# PR9027.net
KiCad netlist of a schematic drawn in EAGLE
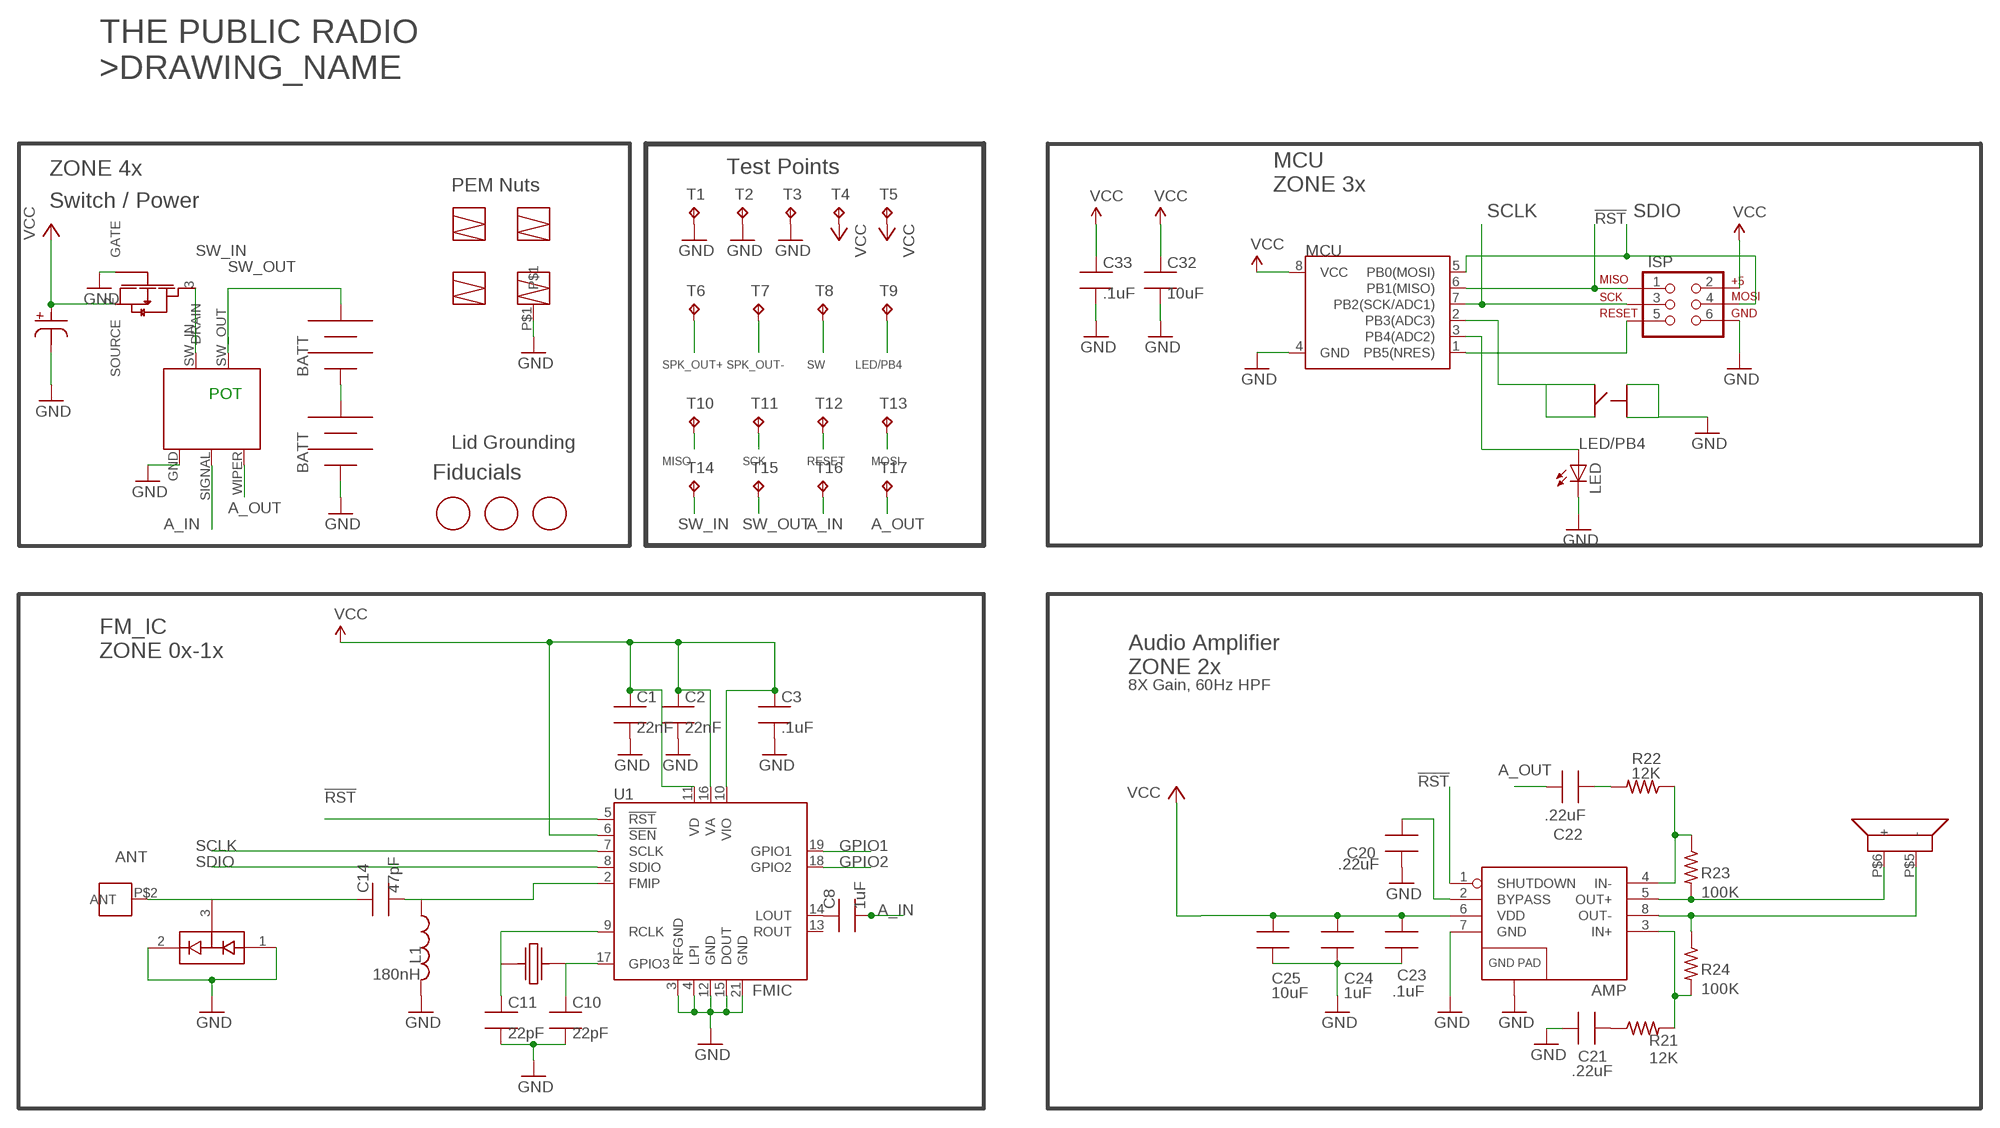
[diagram p0: schematic, sheet 1]

(export (version "E")
  (design (tool "Eeschema 10.0.6"))
  (components
    (comp (ref "AMP")
      (value "TPA6203A1")
      (footprint "eagle-import:8-MSOP")
      (libsource (lib "eagle-import") (part "TPA6203A1"))
    )
    (comp (ref "ANT_MOUNT")
      (value "PEM_M3")
      (footprint "eagle-import:PEM_M3")
      (libsource (lib "eagle-import") (part "PEM_M3"))
    )
    (comp (ref "C1")
      (value "22nF")
      (footprint "eagle-import:0603_CPL")
      (fields
        (field (name "MFG_PN") "CL10B223KB8NNNC")
        (field (name "TOL") "10%")
        (field (name "VOLTAGE") "16V")
      )
      (libsource (lib "eagle-import") (part "C_SMT_0603_CPL"))
    )
    (comp (ref "C2")
      (value "22nF")
      (footprint "eagle-import:0603_CPL")
      (fields
        (field (name "MFG_PN") "CL10B223KB8NNNC")
        (field (name "TOL") "10%")
        (field (name "VOLTAGE") "16V")
      )
      (libsource (lib "eagle-import") (part "C_SMT_0603_CPL"))
    )
    (comp (ref "C3")
      (value ".1uF")
      (footprint "eagle-import:0603_CPL")
      (fields
        (field (name "MFG_PN") "CL10B104KB8SFNC")
        (field (name "TOL") "10%")
        (field (name "VOLTAGE") "16V")
      )
      (libsource (lib "eagle-import") (part "C_SMT_0603_CPL"))
    )
    (comp (ref "C8")
      (value "1uF")
      (footprint "eagle-import:0603_CPL")
      (fields
        (field (name "MFG_PN") "CL10B105KP8NNNC")
        (field (name "TOL") "10%")
        (field (name "VOLTAGE") "10V")
      )
      (libsource (lib "eagle-import") (part "C_SMT_0603_CPL"))
    )
    (comp (ref "C10")
      (value "22pF")
      (footprint "eagle-import:0603_CPL")
      (fields
        (field (name "MFG_PN") "C1608C0G1H220J080AA")
        (field (name "TOL") "5%")
        (field (name "VOLTAGE") "50V")
      )
      (libsource (lib "eagle-import") (part "C_SMT_0603_CPL"))
    )
    (comp (ref "C11")
      (value "22pF")
      (footprint "eagle-import:0603_CPL")
      (fields
        (field (name "MFG_PN") "C1608C0G1H220J080AA")
        (field (name "TOL") "5%")
        (field (name "VOLTAGE") "50V")
      )
      (libsource (lib "eagle-import") (part "C_SMT_0603_CPL"))
    )
    (comp (ref "C14")
      (value "47pF")
      (footprint "eagle-import:0603_CPL")
      (fields
        (field (name "MFG_PN") "CL10C470JB8NCNC")
        (field (name "TOL") "5%")
        (field (name "VOLTAGE") "50V")
      )
      (libsource (lib "eagle-import") (part "C_SMT_0603_CPL"))
    )
    (comp (ref "C20")
      (value ".22uF")
      (footprint "eagle-import:0603_CPL")
      (fields
        (field (name "MFG_PN") "C1608X7R1C224K080AC")
        (field (name "TOL") "10%")
        (field (name "VOLTAGE") "16V")
      )
      (libsource (lib "eagle-import") (part "C_SMT_0603_CPL"))
    )
    (comp (ref "C21")
      (value ".22uF")
      (footprint "eagle-import:0603_CPL")
      (fields
        (field (name "MFG_PN") "C1608X7R1C224K080AC")
        (field (name "TOL") "10%")
        (field (name "VOLTAGE") "16V")
      )
      (libsource (lib "eagle-import") (part "C_SMT_0603_CPL"))
    )
    (comp (ref "C22")
      (value ".22uF")
      (footprint "eagle-import:0603_CPL")
      (fields
        (field (name "MFG_PN") "C1608X7R1C224K080AC")
        (field (name "TOL") "10%")
        (field (name "VOLTAGE") "16V")
      )
      (libsource (lib "eagle-import") (part "C_SMT_0603_CPL"))
    )
    (comp (ref "C23")
      (value ".1uF")
      (footprint "eagle-import:0603_CPL")
      (fields
        (field (name "MFG_PN") "CL10B104KB8SFNC")
        (field (name "TOL") "10%")
        (field (name "VOLTAGE") "16V")
      )
      (libsource (lib "eagle-import") (part "C_SMT_0603_CPL"))
    )
    (comp (ref "C24")
      (value "1uF")
      (footprint "eagle-import:0603_CPL")
      (fields
        (field (name "MFG_PN") "CL10B105KP8NNNC")
        (field (name "TOL") "10%")
        (field (name "VOLTAGE") "10V")
      )
      (libsource (lib "eagle-import") (part "C_SMT_0603_CPL"))
    )
    (comp (ref "C25")
      (value "10uF")
      (footprint "eagle-import:0603_CPL")
      (fields
        (field (name "MFG_PN") "CL10A106MQ8NNNC")
        (field (name "TOL") "20%")
        (field (name "VOLTAGE") "6.3V")
      )
      (libsource (lib "eagle-import") (part "C_SMT_0603_CPL"))
    )
    (comp (ref "C32")
      (value "10uF")
      (footprint "eagle-import:0603_CPL")
      (fields
        (field (name "MFG_PN") "CL10A106MQ8NNNC")
        (field (name "TOL") "20%")
        (field (name "VOLTAGE") "6.3V")
      )
      (libsource (lib "eagle-import") (part "C_SMT_0603_CPL"))
    )
    (comp (ref "C33")
      (value ".1uF")
      (footprint "eagle-import:0603_CPL")
      (fields
        (field (name "MFG_PN") "CL10B104KB8SFNC")
        (field (name "TOL") "10%")
        (field (name "VOLTAGE") "16V")
      )
      (libsource (lib "eagle-import") (part "C_SMT_0603_CPL"))
    )
    (comp (ref "C40")
      (value "220uF")
      (footprint "eagle-import:NICHICON_UD_63")
      (fields (field (name "TOL") "20%") (field (name "VOLTAGE") "16V"))
      (libsource (lib "eagle-import") (part "NICHICON_SERIESUD"))
    )
    (comp (ref "D1")
      (value "BAV99")
      (footprint "eagle-import:SOT23_CPL")
      (fields (field (name "MFG_PN") "BAV99,215"))
      (libsource (lib "eagle-import") (part "BAV99"))
    )
    (comp (ref "FET1")
      (value "AO3435")
      (footprint "eagle-import:SOT23_CPL")
      (fields (field (name "MFG_PN") "AO3435"))
      (libsource (lib "eagle-import") (part "AO3435"))
    )
    (comp (ref "ISP")
      (value "AVR_SPI_PRG_6NS")
      (footprint "eagle-import:2X3-NS")
      (fields (field (name "MFG_PN") "DNP"))
      (libsource (lib "eagle-import") (part "AVR_SPI_PRG_6NS"))
    )
    (comp (ref "JP5")
      (value "BK-92_MPD_AA_BATT_CLIP")
      (footprint "eagle-import:BK92_AA_BATT")
      (fields (field (name "MFG_PN") "Consigned"))
      (libsource (lib "eagle-import") (part "BK-92_MPD_AA_BATT_CLIP"))
    )
    (comp (ref "JP6")
      (value "BK-92_MPD_AA_BATT_CLIP")
      (footprint "eagle-import:BK92_AA_BATT")
      (fields (field (name "MFG_PN") "Consigned"))
      (libsource (lib "eagle-import") (part "BK-92_MPD_AA_BATT_CLIP"))
    )
    (comp (ref "L1")
      (value "180nH")
      (footprint "eagle-import:0805_ADAFRUIT")
      (fields
        (field (name "CURRENT") "400mA")
        (field (name "DCR") "640m")
        (field (name "MFG_PN") "AISC-0805-R18J-T ")
        (field (name "TOL") "5%")
      )
      (libsource (lib "eagle-import") (part "L_SMT_0805_ADAFRUIT"))
    )
    (comp (ref "LED")
      (value "HSMC-C265_REVERSE_MOUNT_LED")
      (footprint "eagle-import:HSMA-C265_REVERSE_MOUN_LED")
      (libsource (lib "eagle-import") (part "HSMC-C265_REVERSE_MOUNT_LED"))
    )
    (comp (ref "MARK1")
      (value "FIDUCIAL")
      (footprint "eagle-import:FIDUCIAL_1MM")
      (libsource (lib "eagle-import") (part "FIDUCIAL"))
    )
    (comp (ref "MARK2")
      (value "FIDUCIAL")
      (footprint "eagle-import:FIDUCIAL_1MM")
      (libsource (lib "eagle-import") (part "FIDUCIAL"))
    )
    (comp (ref "MARK3")
      (value "FIDUCIAL")
      (footprint "eagle-import:FIDUCIAL_1MM")
      (libsource (lib "eagle-import") (part "FIDUCIAL"))
    )
    (comp (ref "MCU")
      (value "ATTINY45TINY45-20-SMT")
      (footprint "eagle-import:8-SOIC")
      (fields (field (name "MFG_PN") "ATTINY25-20SUR "))
      (libsource (lib "eagle-import") (part "ATTINY45TINY45-20-SMT"))
    )
    (comp (ref "R1")
      (value "VOLUME_POT")
      (footprint "eagle-import:H17112NS_A10K_L20F-002")
      (libsource (lib "eagle-import") (part "VOLUME_POT"))
    )
    (comp (ref "R21")
      (value "12K")
      (footprint "eagle-import:0603_CPL")
      (fields
        (field (name "MFG_PN") "RC0603FR-0712KL")
        (field (name "POWER") "1/10W")
        (field (name "TOL") "1%")
      )
      (libsource (lib "eagle-import") (part "R_SMT_R0603_CPL"))
    )
    (comp (ref "R22")
      (value "12K")
      (footprint "eagle-import:0603_CPL")
      (fields
        (field (name "MFG_PN") "RC0603FR-0712KL")
        (field (name "POWER") "1/10W")
        (field (name "TOL") "1%")
      )
      (libsource (lib "eagle-import") (part "R_SMT_R0603_CPL"))
    )
    (comp (ref "R23")
      (value "100K")
      (footprint "eagle-import:0603_CPL")
      (fields
        (field (name "MFG_PN") "ERJ-3EKF1003V")
        (field (name "POWER") "1/10W")
        (field (name "TOL") "1%")
      )
      (libsource (lib "eagle-import") (part "R_SMT_R0603_CPL"))
    )
    (comp (ref "R24")
      (value "100K")
      (footprint "eagle-import:0603_CPL")
      (fields
        (field (name "MFG_PN") "ERJ-3EKF1003V")
        (field (name "POWER") "1/10W")
        (field (name "TOL") "1%")
      )
      (libsource (lib "eagle-import") (part "R_SMT_R0603_CPL"))
    )
    (comp (ref "SPEAKER")
      (value "PR2023_GROUND_UP_SPEAKER")
      (footprint "eagle-import:PR2023_GROUND_UP_SPEAKER")
      (libsource (lib "eagle-import") (part "PR2023_GROUND_UP_SPEAKER"))
    )
    (comp (ref "SPEAKER_PEM_1")
      (value "PEM_M3_ONE_SIDE")
      (footprint "eagle-import:PEM_M3_ONE_SIDE")
      (libsource (lib "eagle-import") (part "PEM_M3_ONE_SIDE"))
    )
    (comp (ref "SPEAKER_PEM_2")
      (value "PEM_M3_ONE_SIDE")
      (footprint "eagle-import:PEM_M3_ONE_SIDE")
      (libsource (lib "eagle-import") (part "PEM_M3_ONE_SIDE"))
    )
    (comp (ref "SPEAKER_PEM_3")
      (value "PEM_M3_ONE_SIDE_W/PIN")
      (footprint "eagle-import:PEM_M3_ONE_SIDE")
      (libsource (lib "eagle-import") (part "PEM_M3_ONE_SIDE_W/PIN"))
    )
    (comp (ref "SPEAKER_PEM_4")
      (value "PEM_M3_ONE_SIDE")
      (footprint "eagle-import:PEM_M3_ONE_SIDE")
      (libsource (lib "eagle-import") (part "PEM_M3_ONE_SIDE"))
    )
    (comp (ref "SW1")
      (value "C&K_PTS645")
      (footprint "eagle-import:C&K_PTS645_SMT")
      (libsource (lib "eagle-import") (part "C&K_PTS645"))
    )
    (comp (ref "T1")
      (value "TPTP20R")
      (footprint "eagle-import:TP20R")
      (libsource (lib "eagle-import") (part "TPTP20R"))
    )
    (comp (ref "T2")
      (value "TPTP20R")
      (footprint "eagle-import:TP20R")
      (libsource (lib "eagle-import") (part "TPTP20R"))
    )
    (comp (ref "T3")
      (value "TPTP20R")
      (footprint "eagle-import:TP20R")
      (libsource (lib "eagle-import") (part "TPTP20R"))
    )
    (comp (ref "T4")
      (value "TPTP20R")
      (footprint "eagle-import:TP20R")
      (libsource (lib "eagle-import") (part "TPTP20R"))
    )
    (comp (ref "T5")
      (value "TPTP20R")
      (footprint "eagle-import:TP20R")
      (libsource (lib "eagle-import") (part "TPTP20R"))
    )
    (comp (ref "T6")
      (value "TPTP20R")
      (footprint "eagle-import:TP20R")
      (libsource (lib "eagle-import") (part "TPTP20R"))
    )
    (comp (ref "T7")
      (value "TPTP20R")
      (footprint "eagle-import:TP20R")
      (libsource (lib "eagle-import") (part "TPTP20R"))
    )
    (comp (ref "T8")
      (value "TPTP20R")
      (footprint "eagle-import:TP20R")
      (libsource (lib "eagle-import") (part "TPTP20R"))
    )
    (comp (ref "T9")
      (value "TPTP20R")
      (footprint "eagle-import:TP20R")
      (libsource (lib "eagle-import") (part "TPTP20R"))
    )
    (comp (ref "T10")
      (value "TPTP20R")
      (footprint "eagle-import:TP20R")
      (libsource (lib "eagle-import") (part "TPTP20R"))
    )
    (comp (ref "T11")
      (value "TPTP20R")
      (footprint "eagle-import:TP20R")
      (libsource (lib "eagle-import") (part "TPTP20R"))
    )
    (comp (ref "T12")
      (value "TPTP20R")
      (footprint "eagle-import:TP20R")
      (libsource (lib "eagle-import") (part "TPTP20R"))
    )
    (comp (ref "T13")
      (value "TPTP20R")
      (footprint "eagle-import:TP20R")
      (libsource (lib "eagle-import") (part "TPTP20R"))
    )
    (comp (ref "T14")
      (value "TPTP20R")
      (footprint "eagle-import:TP20R")
      (libsource (lib "eagle-import") (part "TPTP20R"))
    )
    (comp (ref "T15")
      (value "TPTP20R")
      (footprint "eagle-import:TP20R")
      (libsource (lib "eagle-import") (part "TPTP20R"))
    )
    (comp (ref "T16")
      (value "TPTP20R")
      (footprint "eagle-import:TP20R")
      (libsource (lib "eagle-import") (part "TPTP20R"))
    )
    (comp (ref "T17")
      (value "TPTP20R")
      (footprint "eagle-import:TP20R")
      (libsource (lib "eagle-import") (part "TPTP20R"))
    )
    (comp (ref "U1")
      (value "FMIC")
      (footprint "eagle-import:SI470X_20_QFN")
      (fields (field (name "MFG_PN") "SI4702-C19-GMR"))
      (libsource (lib "eagle-import") (part "SI4702-C19-GMR"))
    )
    (comp (ref "X1")
      (value "ABS25XTAL")
      (footprint "eagle-import:4-SOJ")
      (libsource (lib "eagle-import") (part "ABS25XTAL"))
    )
  )
  (nets
    (net (code "1") (name "/ANT") (class "Default")
      (node (ref "ANT_MOUNT") (pin "P$2") (pinfunction "ANT_P$2") (pintype "bidirectional"))
      (node (ref "C14") (pin "1") (pinfunction "1_1") (pintype "passive"))
      (node (ref "D1") (pin "3") (pinfunction "COM_3") (pintype "bidirectional"))
    )
    (net (code "2") (name "/A_IN") (class "Default")
      (node (ref "C8") (pin "2") (pinfunction "2_2") (pintype "passive"))
      (node (ref "R1") (pin "SIGNAL") (pinfunction "SIGNAL_SIGNAL") (pintype "bidirectional"))
      (node (ref "T16") (pin "TP") (pinfunction "TP_TP") (pintype "input"))
    )
    (net (code "3") (name "/A_OUT") (class "Default")
      (node (ref "C22") (pin "2") (pinfunction "2_2") (pintype "passive"))
      (node (ref "R1") (pin "WIPER") (pinfunction "WIPER_WIPER") (pintype "bidirectional"))
      (node (ref "T17") (pin "TP") (pinfunction "TP_TP") (pintype "input"))
    )
    (net (code "4") (name "/GPIO1") (class "Default")
      (node (ref "U1") (pin "19") (pinfunction "GPIO1_19") (pintype "bidirectional"))
    )
    (net (code "5") (name "/GPIO2") (class "Default")
      (node (ref "U1") (pin "18") (pinfunction "GPIO2_18") (pintype "bidirectional"))
    )
    (net (code "6") (name "/LED{slash}PB4") (class "Default")
      (node (ref "LED") (pin "P$1") (pinfunction "A_P$1") (pintype "passive"))
      (node (ref "MCU") (pin "3") (pinfunction "PB4(ADC2)_3") (pintype "bidirectional"))
      (node (ref "T9") (pin "TP") (pinfunction "TP_TP") (pintype "input"))
    )
    (net (code "7") (name "/RESET") (class "Default")
      (node (ref "ISP") (pin "5") (pinfunction "5_5") (pintype "passive"))
      (node (ref "MCU") (pin "1") (pinfunction "PB5(NRES)_1") (pintype "bidirectional"))
      (node (ref "T12") (pin "TP") (pinfunction "TP_TP") (pintype "input"))
    )
    (net (code "8") (name "/SCLK") (class "Default")
      (node (ref "ISP") (pin "3") (pinfunction "3_3") (pintype "passive"))
      (node (ref "MCU") (pin "7") (pinfunction "PB2(SCK/ADC1)_7") (pintype "bidirectional"))
      (node (ref "T11") (pin "TP") (pinfunction "TP_TP") (pintype "input"))
      (node (ref "U1") (pin "7") (pinfunction "SCLK_7") (pintype "bidirectional"))
    )
    (net (code "9") (name "/SDIO") (class "Default")
      (node (ref "ISP") (pin "4") (pinfunction "4_4") (pintype "passive"))
      (node (ref "MCU") (pin "5") (pinfunction "PB0(MOSI)_5") (pintype "bidirectional"))
      (node (ref "T13") (pin "TP") (pinfunction "TP_TP") (pintype "input"))
      (node (ref "U1") (pin "8") (pinfunction "SDIO_8") (pintype "bidirectional"))
    )
    (net (code "10") (name "/SPK_OUT+") (class "Default")
      (node (ref "AMP") (pin "5") (pinfunction "OUT+_5") (pintype "bidirectional"))
      (node (ref "R23") (pin "2") (pinfunction "2_2") (pintype "passive"))
      (node (ref "SPEAKER") (pin "P$6") (pinfunction "+_P$6") (pintype "bidirectional"))
      (node (ref "T6") (pin "TP") (pinfunction "TP_TP") (pintype "input"))
    )
    (net (code "11") (name "/SPK_OUT-") (class "Default")
      (node (ref "AMP") (pin "8") (pinfunction "OUT-_8") (pintype "bidirectional"))
      (node (ref "R24") (pin "1") (pinfunction "1_1") (pintype "passive"))
      (node (ref "SPEAKER") (pin "P$5") (pinfunction "-_P$5") (pintype "bidirectional"))
      (node (ref "T7") (pin "TP") (pinfunction "TP_TP") (pintype "input"))
    )
    (net (code "12") (name "/SW") (class "Default")
      (node (ref "MCU") (pin "2") (pinfunction "PB3(ADC3)_2") (pintype "bidirectional"))
      (node (ref "SW1") (pin "P$3") (pinfunction "P$3_P$3") (pintype "bidirectional"))
      (node (ref "SW1") (pin "P$4") (pinfunction "P$4_P$4") (pintype "bidirectional"))
      (node (ref "T8") (pin "TP") (pinfunction "TP_TP") (pintype "input"))
    )
    (net (code "13") (name "/SW_IN") (class "Default")
      (node (ref "FET1") (pin "3") (pinfunction "DRAIN_3") (pintype "bidirectional"))
      (node (ref "R1") (pin "SW_IN") (pinfunction "SW_IN_SW_IN") (pintype "bidirectional"))
      (node (ref "T14") (pin "TP") (pinfunction "TP_TP") (pintype "input"))
    )
    (net (code "14") (name "/SW_OUT") (class "Default")
      (node (ref "JP5") (pin "POS") (pinfunction "POS_POS") (pintype "bidirectional"))
      (node (ref "JP5") (pin "POS@2") (pinfunction "POS_POS@2") (pintype "bidirectional"))
      (node (ref "R1") (pin "SW_OUT") (pinfunction "SW_OUT_SW_OUT") (pintype "bidirectional"))
      (node (ref "T15") (pin "TP") (pinfunction "TP_TP") (pintype "input"))
    )
    (net (code "15") (name "/~{RST}") (class "Default")
      (node (ref "AMP") (pin "1") (pinfunction "SHUTDOWN_1") (pintype "input"))
      (node (ref "ISP") (pin "1") (pinfunction "1_1") (pintype "passive"))
      (node (ref "MCU") (pin "6") (pinfunction "PB1(MISO)_6") (pintype "bidirectional"))
      (node (ref "T10") (pin "TP") (pinfunction "TP_TP") (pintype "input"))
      (node (ref "U1") (pin "5") (pinfunction "~{RST}_5") (pintype "bidirectional"))
    )
    (net (code "16") (name "GND") (class "Default")
      (node (ref "AMP") (pin "7") (pinfunction "GND_7") (pintype "power_in"))
      (node (ref "AMP") (pin "9") (pinfunction "GND_9") (pintype "power_in"))
      (node (ref "C1") (pin "2") (pinfunction "2_2") (pintype "passive"))
      (node (ref "C10") (pin "2") (pinfunction "2_2") (pintype "passive"))
      (node (ref "C11") (pin "2") (pinfunction "2_2") (pintype "passive"))
      (node (ref "C2") (pin "2") (pinfunction "2_2") (pintype "passive"))
      (node (ref "C20") (pin "1") (pinfunction "1_1") (pintype "passive"))
      (node (ref "C21") (pin "1") (pinfunction "1_1") (pintype "passive"))
      (node (ref "C23") (pin "2") (pinfunction "2_2") (pintype "passive"))
      (node (ref "C24") (pin "2") (pinfunction "2_2") (pintype "passive"))
      (node (ref "C25") (pin "2") (pinfunction "2_2") (pintype "passive"))
      (node (ref "C3") (pin "2") (pinfunction "2_2") (pintype "passive"))
      (node (ref "C32") (pin "2") (pinfunction "2_2") (pintype "passive"))
      (node (ref "C33") (pin "2") (pinfunction "2_2") (pintype "passive"))
      (node (ref "C40") (pin "P$2") (pinfunction "P$2_P$2") (pintype "bidirectional"))
      (node (ref "D1") (pin "1") (pinfunction "A1_1") (pintype "bidirectional"))
      (node (ref "D1") (pin "2") (pinfunction "C2_2") (pintype "bidirectional"))
      (node (ref "FET1") (pin "1") (pinfunction "GATE_1") (pintype "bidirectional"))
      (node (ref "ISP") (pin "6") (pinfunction "6_6") (pintype "passive"))
      (node (ref "JP6") (pin "NEG") (pinfunction "NEG_NEG") (pintype "bidirectional"))
      (node (ref "JP6") (pin "NEG@2") (pinfunction "NEG_NEG@2") (pintype "bidirectional"))
      (node (ref "L1") (pin "2") (pinfunction "2_2") (pintype "passive"))
      (node (ref "LED") (pin "P$2") (pinfunction "C_P$2") (pintype "passive"))
      (node (ref "MCU") (pin "4") (pinfunction "GND_4") (pintype "bidirectional"))
      (node (ref "R1") (pin "GND") (pinfunction "GND_GND") (pintype "bidirectional"))
      (node (ref "SPEAKER_PEM_3") (pin "P$1") (pinfunction "P$1_P$1") (pintype "bidirectional"))
      (node (ref "SW1") (pin "P$1") (pinfunction "P$1_P$1") (pintype "bidirectional"))
      (node (ref "SW1") (pin "P$2") (pinfunction "P$2_P$2") (pintype "bidirectional"))
      (node (ref "T1") (pin "TP") (pinfunction "TP_TP") (pintype "input"))
      (node (ref "T2") (pin "TP") (pinfunction "TP_TP") (pintype "input"))
      (node (ref "T3") (pin "TP") (pinfunction "TP_TP") (pintype "input"))
      (node (ref "U1") (pin "12") (pinfunction "GND_12") (pintype "bidirectional"))
      (node (ref "U1") (pin "15") (pinfunction "DOUT_15") (pintype "bidirectional"))
      (node (ref "U1") (pin "21") (pinfunction "GND_21") (pintype "bidirectional"))
      (node (ref "U1") (pin "3") (pinfunction "RFGND_3") (pintype "bidirectional"))
      (node (ref "U1") (pin "4") (pinfunction "LPI_4") (pintype "bidirectional"))
    )
    (net (code "17") (name "Net-(AMP-BYPASS)") (class "Default")
      (node (ref "AMP") (pin "2") (pinfunction "BYPASS_2") (pintype "bidirectional"))
      (node (ref "C20") (pin "2") (pinfunction "2_2") (pintype "passive"))
    )
    (net (code "18") (name "Net-(AMP-IN+)") (class "Default")
      (node (ref "AMP") (pin "3") (pinfunction "IN+_3") (pintype "bidirectional"))
      (node (ref "R21") (pin "2") (pinfunction "2_2") (pintype "passive"))
      (node (ref "R24") (pin "2") (pinfunction "2_2") (pintype "passive"))
    )
    (net (code "19") (name "Net-(AMP-IN-)") (class "Default")
      (node (ref "AMP") (pin "4") (pinfunction "IN-_4") (pintype "bidirectional"))
      (node (ref "R22") (pin "1") (pinfunction "1_1") (pintype "passive"))
      (node (ref "R23") (pin "1") (pinfunction "1_1") (pintype "passive"))
    )
    (net (code "20") (name "Net-(C21-Pad2)") (class "Default")
      (node (ref "C21") (pin "2") (pinfunction "2_2") (pintype "passive"))
      (node (ref "R21") (pin "1") (pinfunction "1_1") (pintype "passive"))
    )
    (net (code "21") (name "Net-(C22-Pad1)") (class "Default")
      (node (ref "C22") (pin "1") (pinfunction "1_1") (pintype "passive"))
      (node (ref "R22") (pin "2") (pinfunction "2_2") (pintype "passive"))
    )
    (net (code "22") (name "Net-(JP5-NEG-PadNEG@2)") (class "Default")
      (node (ref "JP5") (pin "NEG") (pinfunction "NEG_NEG") (pintype "bidirectional"))
      (node (ref "JP5") (pin "NEG@2") (pinfunction "NEG_NEG@2") (pintype "bidirectional"))
      (node (ref "JP6") (pin "POS") (pinfunction "POS_POS") (pintype "bidirectional"))
      (node (ref "JP6") (pin "POS@2") (pinfunction "POS_POS@2") (pintype "bidirectional"))
    )
    (net (code "23") (name "Net-(U1-FMIP)") (class "Default")
      (node (ref "C14") (pin "2") (pinfunction "2_2") (pintype "passive"))
      (node (ref "L1") (pin "1") (pinfunction "1_1") (pintype "passive"))
      (node (ref "U1") (pin "2") (pinfunction "FMIP_2") (pintype "bidirectional"))
    )
    (net (code "24") (name "Net-(U1-GPIO3)") (class "Default")
      (node (ref "C10") (pin "1") (pinfunction "1_1") (pintype "passive"))
      (node (ref "U1") (pin "17") (pinfunction "GPIO3_17") (pintype "bidirectional"))
      (node (ref "X1") (pin "P$4") (pinfunction "P$4_P$4") (pintype "bidirectional"))
    )
    (net (code "25") (name "Net-(U1-LOUT)") (class "Default")
      (node (ref "C8") (pin "1") (pinfunction "1_1") (pintype "passive"))
      (node (ref "U1") (pin "14") (pinfunction "LOUT_14") (pintype "bidirectional"))
    )
    (net (code "26") (name "Net-(U1-RCLK)") (class "Default")
      (node (ref "C11") (pin "1") (pinfunction "1_1") (pintype "passive"))
      (node (ref "U1") (pin "9") (pinfunction "RCLK_9") (pintype "bidirectional"))
      (node (ref "X1") (pin "P$1") (pinfunction "P$1_P$1") (pintype "bidirectional"))
    )
    (net (code "27") (name "VCC") (class "Default")
      (node (ref "AMP") (pin "6") (pinfunction "VDD_6") (pintype "power_in"))
      (node (ref "C1") (pin "1") (pinfunction "1_1") (pintype "passive"))
      (node (ref "C2") (pin "1") (pinfunction "1_1") (pintype "passive"))
      (node (ref "C23") (pin "1") (pinfunction "1_1") (pintype "passive"))
      (node (ref "C24") (pin "1") (pinfunction "1_1") (pintype "passive"))
      (node (ref "C25") (pin "1") (pinfunction "1_1") (pintype "passive"))
      (node (ref "C3") (pin "1") (pinfunction "1_1") (pintype "passive"))
      (node (ref "C32") (pin "1") (pinfunction "1_1") (pintype "passive"))
      (node (ref "C33") (pin "1") (pinfunction "1_1") (pintype "passive"))
      (node (ref "C40") (pin "P$1") (pinfunction "P$1_P$1") (pintype "bidirectional"))
      (node (ref "FET1") (pin "2") (pinfunction "SOURCE_2") (pintype "bidirectional"))
      (node (ref "ISP") (pin "2") (pinfunction "2_2") (pintype "passive"))
      (node (ref "MCU") (pin "8") (pinfunction "VCC_8") (pintype "bidirectional"))
      (node (ref "T4") (pin "TP") (pinfunction "TP_TP") (pintype "input"))
      (node (ref "T5") (pin "TP") (pinfunction "TP_TP") (pintype "input"))
      (node (ref "U1") (pin "10") (pinfunction "VIO_10") (pintype "bidirectional"))
      (node (ref "U1") (pin "11") (pinfunction "VD_11") (pintype "bidirectional"))
      (node (ref "U1") (pin "16") (pinfunction "VA_16") (pintype "bidirectional"))
      (node (ref "U1") (pin "6") (pinfunction "~{SEN}_6") (pintype "bidirectional"))
    )
    (net (code "28") (name "unconnected-(U1-ROUT-Pad13)") (class "Default")
      (node (ref "U1") (pin "13") (pinfunction "ROUT_13") (pintype "bidirectional"))
    )
  )
)
